# Sheet4.net
KiCad netlist of a schematic drawn in Altium Designer
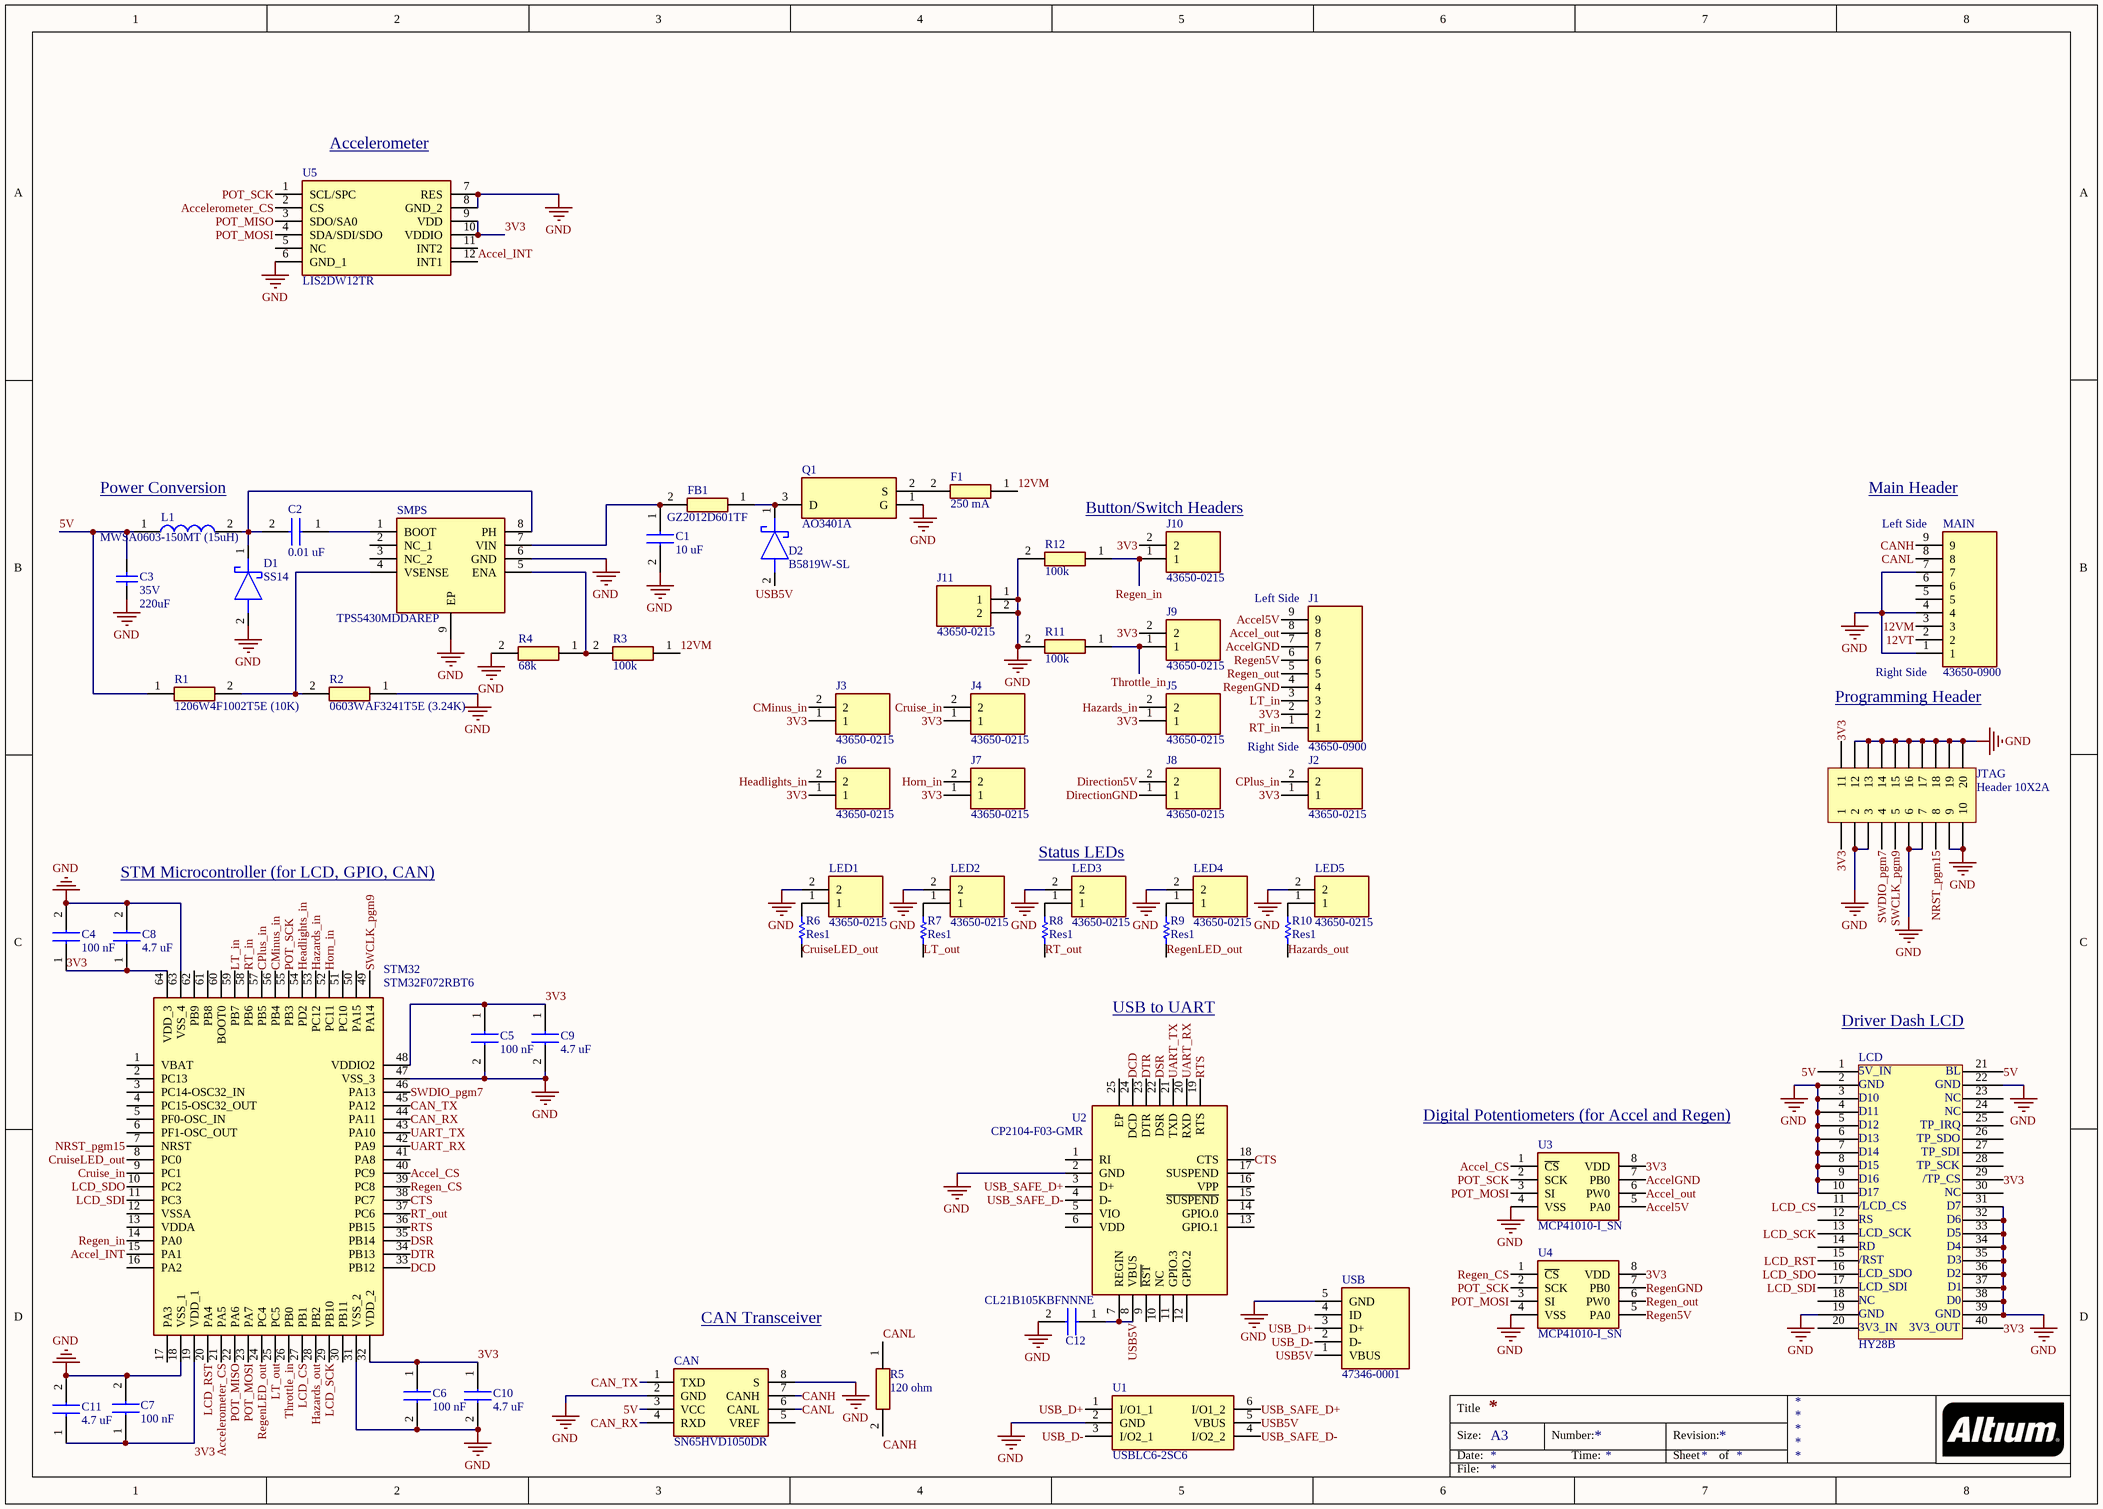
[diagram p0: Sheet4.SchDoc]

(export (version "E")
  (design (tool "Eeschema 10.0.6"))
  (components
    (comp (ref "C1")
      (value "10 uF")
      (footprint "SamacSys:CAPC2012X145N")
      (description "Capacitor")
      (fields (field (name "MANUFACTURER_PART_NUMBER") "CL21A106KAYNNNE"))
      (libsource (lib "*") (part "CL21A106KAYNNNE"))
    )
    (comp (ref "C2")
      (value "0.01 uF")
      (footprint "SamacSys:CAPC2012X65N")
      (description "Capacitor")
      (fields (field (name "MANUFACTURER_PART_NUMBER") "CL21B103KBANNNC"))
      (libsource (lib "*") (part "CL21B103KBANNNC"))
    )
    (comp (ref "C3")
      (value "35V")
      (footprint "RAD-0.3")
      (description "Capacitor")
      (fields (field (name "ALTIUM_VALUE") "220uF") (field (name "PUBLISHER") "Altium Limited"))
      (libsource (lib "Miscellaneous Devices") (part "Cap"))
    )
    (comp (ref "C4")
      (value "100 nF")
      (footprint "SamacSys:CAPC1005X55N")
      (description "Capacitor")
      (fields (field (name "MANUFACTURER_PART_NUMBER") "CL05B104KO5NNNC"))
      (libsource (lib "*") (part "CL05B104KO5NNNC"))
    )
    (comp (ref "C5")
      (value "100 nF")
      (footprint "SamacSys:CAPC1005X55N")
      (description "Capacitor")
      (fields (field (name "MANUFACTURER_PART_NUMBER") "CL05B104KO5NNNC"))
      (libsource (lib "*") (part "CL05B104KO5NNNC"))
    )
    (comp (ref "C6")
      (value "100 nF")
      (footprint "SamacSys:CAPC1005X55N")
      (description "Capacitor")
      (fields (field (name "MANUFACTURER_PART_NUMBER") "CL05B104KO5NNNC"))
      (libsource (lib "*") (part "CL05B104KO5NNNC"))
    )
    (comp (ref "C7")
      (value "100 nF")
      (footprint "SamacSys:CAPC1005X55N")
      (description "Capacitor")
      (fields (field (name "MANUFACTURER_PART_NUMBER") "CL05B104KO5NNNC"))
      (libsource (lib "*") (part "CL05B104KO5NNNC"))
    )
    (comp (ref "C8")
      (value "4.7 uF")
      (footprint "SamacSys:CAPC2012X140N")
      (description "Capacitor")
      (fields (field (name "MANUFACTURER_PART_NUMBER") "CL21A475KAQNNNE"))
      (libsource (lib "*") (part "CL21A475KAQNNNE"))
    )
    (comp (ref "C9")
      (value "4.7 uF")
      (footprint "SamacSys:CAPC2012X140N")
      (description "Capacitor")
      (fields (field (name "MANUFACTURER_PART_NUMBER") "CL21A475KAQNNNE"))
      (libsource (lib "*") (part "CL21A475KAQNNNE"))
    )
    (comp (ref "C10")
      (value "4.7 uF")
      (footprint "SamacSys:CAPC2012X140N")
      (description "Capacitor")
      (fields (field (name "MANUFACTURER_PART_NUMBER") "CL21A475KAQNNNE"))
      (libsource (lib "*") (part "CL21A475KAQNNNE"))
    )
    (comp (ref "C11")
      (value "4.7 uF")
      (footprint "SamacSys:CAPC2012X140N")
      (description "Capacitor")
      (fields (field (name "MANUFACTURER_PART_NUMBER") "CL21A475KAQNNNE"))
      (libsource (lib "*") (part "CL21A475KAQNNNE"))
    )
    (comp (ref "C12")
      (value "CL21B105KBFNNNE")
      (footprint "SamacSys:CAPC2012X135N")
      (description "Capacitor")
      (libsource (lib "*") (part "CL21B105KBFNNNE"))
    )
    (comp (ref "CAN")
      (value "SN65HVD1050DR")
      (footprint "SamacSys:SOIC127P600X175-8N")
      (description "Integrated Circuit")
      (libsource (lib "*") (part "SN65HVD1050DR"))
    )
    (comp (ref "D1")
      (value "SS14")
      (footprint "SamacSys:DIONM5327X242N")
      (description "Schottky Diode")
      (libsource (lib "*") (part "SS14"))
    )
    (comp (ref "D2")
      (value "B5819W-SL")
      (footprint "SamacSys:SOD3716X135N")
      (description "Schottky Diode")
      (fields (field (name "MANUFACTURER_PART_NUMBER") "B5819W-TP"))
      (libsource (lib "*") (part "B5819W-TP"))
    )
    (comp (ref "F1")
      (value "250 mA")
      (footprint "SamacSys:RESC3216X51N")
      (description "Resistor")
      (fields (field (name "MANUFACTURER_PART_NUMBER") "PHPA1206E2001BST1"))
      (libsource (lib "*") (part "PHPA1206E2001BST1"))
    )
    (comp (ref "FB1")
      (value "GZ2012D601TF")
      (footprint "SamacSys:RESC2012X55N")
      (description "Resistor")
      (fields (field (name "MANUFACTURER_PART_NUMBER") "TNPU080550K0AZEN00"))
      (libsource (lib "*") (part "TNPU080550K0AZEN00"))
    )
    (comp (ref "J1")
      (value "43650-0900")
      (footprint "SamacSys:436500900")
      (description "Connector")
      (libsource (lib "*") (part "43650-0900"))
    )
    (comp (ref "J2")
      (value "43650-0215")
      (footprint "SamacSys:43650-0217")
      (description "Connector")
      (fields (field (name "MOUSER2 PART NUMBER") "538-43650-0215"))
      (libsource (lib "*") (part "43650-0215"))
    )
    (comp (ref "J3")
      (value "43650-0215")
      (footprint "SamacSys:43650-0217")
      (description "Connector")
      (fields (field (name "MOUSER2 PART NUMBER") "538-43650-0215"))
      (libsource (lib "*") (part "43650-0215"))
    )
    (comp (ref "J4")
      (value "43650-0215")
      (footprint "SamacSys:43650-0217")
      (description "Connector")
      (fields (field (name "MOUSER2 PART NUMBER") "538-43650-0215"))
      (libsource (lib "*") (part "43650-0215"))
    )
    (comp (ref "J5")
      (value "43650-0215")
      (footprint "SamacSys:43650-0217")
      (description "Connector")
      (fields (field (name "MOUSER2 PART NUMBER") "538-43650-0215"))
      (libsource (lib "*") (part "43650-0215"))
    )
    (comp (ref "J6")
      (value "43650-0215")
      (footprint "SamacSys:43650-0217")
      (description "Connector")
      (fields (field (name "MOUSER2 PART NUMBER") "538-43650-0215"))
      (libsource (lib "*") (part "43650-0215"))
    )
    (comp (ref "J7")
      (value "43650-0215")
      (footprint "SamacSys:43650-0217")
      (description "Connector")
      (fields (field (name "MOUSER2 PART NUMBER") "538-43650-0215"))
      (libsource (lib "*") (part "43650-0215"))
    )
    (comp (ref "J8")
      (value "43650-0215")
      (footprint "SamacSys:43650-0217")
      (description "Connector")
      (fields (field (name "MOUSER2 PART NUMBER") "538-43650-0215"))
      (libsource (lib "*") (part "43650-0215"))
    )
    (comp (ref "J9")
      (value "43650-0215")
      (footprint "SamacSys:43650-0217")
      (description "Connector")
      (fields (field (name "MOUSER2 PART NUMBER") "538-43650-0215"))
      (libsource (lib "*") (part "43650-0215"))
    )
    (comp (ref "J10")
      (value "43650-0215")
      (footprint "SamacSys:43650-0217")
      (description "Connector")
      (fields (field (name "MOUSER2 PART NUMBER") "538-43650-0215"))
      (libsource (lib "*") (part "43650-0215"))
    )
    (comp (ref "J11")
      (value "43650-0215")
      (footprint "SamacSys:43650-0217")
      (description "Connector")
      (fields (field (name "MOUSER2 PART NUMBER") "538-43650-0215"))
      (libsource (lib "") (part "43650-0215_1"))
    )
    (comp (ref "JTAG")
      (value "Header 10X2A")
      (footprint "HDR2X10_CEN")
      (description "Header, 10-Pin, Dual row")
      (fields (field (name "PUBLISHER") "Altium Limited"))
      (libsource (lib "Miscellaneous Connectors") (part "Header 10X2A"))
    )
    (comp (ref "L1")
      (value "MWSA0603-150MT (15uH)")
      (footprint "SamacSys:INDPM7166X300N")
      (description "Inductor")
      (fields (field (name "MANUFACTURER_PART_NUMBER") "SRP7028AA-220M"))
      (libsource (lib "*") (part "SRP7028AA-220M"))
    )
    (comp (ref "LCD")
      (value "HY28B")
      (footprint "HY28B")
      (description "2.8\" LCD")
      (libsource (lib "SteeringWheelParts") (part "HY28B"))
    )
    (comp (ref "LED1")
      (value "43650-0215")
      (footprint "SamacSys:43650-0217")
      (description "Connector")
      (fields (field (name "MOUSER2 PART NUMBER") "538-43650-0215"))
      (libsource (lib "*") (part "43650-0215"))
    )
    (comp (ref "LED2")
      (value "43650-0215")
      (footprint "SamacSys:43650-0217")
      (description "Connector")
      (fields (field (name "MOUSER2 PART NUMBER") "538-43650-0215"))
      (libsource (lib "*") (part "43650-0215"))
    )
    (comp (ref "LED3")
      (value "43650-0215")
      (footprint "SamacSys:43650-0217")
      (description "Connector")
      (fields (field (name "MOUSER2 PART NUMBER") "538-43650-0215"))
      (libsource (lib "*") (part "43650-0215"))
    )
    (comp (ref "LED4")
      (value "43650-0215")
      (footprint "SamacSys:43650-0217")
      (description "Connector")
      (fields (field (name "MOUSER2 PART NUMBER") "538-43650-0215"))
      (libsource (lib "*") (part "43650-0215"))
    )
    (comp (ref "LED5")
      (value "43650-0215")
      (footprint "SamacSys:43650-0217")
      (description "Connector")
      (fields (field (name "MOUSER2 PART NUMBER") "538-43650-0215"))
      (libsource (lib "*") (part "43650-0215"))
    )
    (comp (ref "MAIN")
      (value "43650-0900")
      (footprint "SamacSys:436500900")
      (description "Connector")
      (libsource (lib "*") (part "43650-0900"))
    )
    (comp (ref "Q1")
      (value "AO3401A")
      (footprint "SamacSys:SOT95P237X115-3N")
      (description "Diode ESD (Bi-directional)")
      (fields (field (name "MANUFACTURER_PART_NUMBER") "AQ3102-02HTG"))
      (libsource (lib "*") (part "AQ3102-02HTG"))
    )
    (comp (ref "R1")
      (value "1206W4F1002T5E (10K)")
      (footprint "SamacSys:RESC3216X75N")
      (description "Resistor")
      (fields (field (name "MANUFACTURER_PART_NUMBER") "CR1206-FW-2214ELF"))
      (libsource (lib "*") (part "CR1206-FW-2214ELF"))
    )
    (comp (ref "R2")
      (value "0603WAF3241T5E (3.24K)")
      (footprint "SamacSys:RESC1608X55N")
      (description "Resistor")
      (fields (field (name "MANUFACTURER_PART_NUMBER") "MCT0603MZ0000ZP500"))
      (libsource (lib "") (part "MCT0603MZ0000ZP500_1"))
    )
    (comp (ref "R3")
      (value "100k")
      (footprint "SamacSys:RESC3216X51N")
      (description "Resistor")
      (fields (field (name "MANUFACTURER_PART_NUMBER") "PHPA1206E2001BST1"))
      (libsource (lib "*") (part "PHPA1206E2001BST1"))
    )
    (comp (ref "R4")
      (value "68k")
      (footprint "SamacSys:RESC1608X55N")
      (description "Resistor")
      (fields (field (name "MANUFACTURER_PART_NUMBER") "MCT0603MZ0000ZP500"))
      (libsource (lib "") (part "MCT0603MZ0000ZP500_1"))
    )
    (comp (ref "R5")
      (value "120 ohm")
      (footprint "SamacSys:RESC1608X55N")
      (description "Resistor")
      (fields (field (name "MANUFACTURER_PART_NUMBER") "MCT0603MZ0000ZP500"))
      (libsource (lib "*") (part "MCT0603MZ0000ZP500"))
    )
    (comp (ref "R6")
      (value "Res1")
      (footprint "AXIAL-0.3")
      (description "Resistor")
      (fields (field (name "PUBLISHER") "Altium Limited"))
      (libsource (lib "Miscellaneous Devices") (part "Res1"))
    )
    (comp (ref "R7")
      (value "Res1")
      (footprint "AXIAL-0.3")
      (description "Resistor")
      (fields (field (name "PUBLISHER") "Altium Limited"))
      (libsource (lib "Miscellaneous Devices") (part "Res1"))
    )
    (comp (ref "R8")
      (value "Res1")
      (footprint "AXIAL-0.3")
      (description "Resistor")
      (fields (field (name "PUBLISHER") "Altium Limited"))
      (libsource (lib "Miscellaneous Devices") (part "Res1"))
    )
    (comp (ref "R9")
      (value "Res1")
      (footprint "AXIAL-0.3")
      (description "Resistor")
      (fields (field (name "PUBLISHER") "Altium Limited"))
      (libsource (lib "Miscellaneous Devices") (part "Res1"))
    )
    (comp (ref "R10")
      (value "Res1")
      (footprint "AXIAL-0.3")
      (description "Resistor")
      (fields (field (name "PUBLISHER") "Altium Limited"))
      (libsource (lib "Miscellaneous Devices") (part "Res1"))
    )
    (comp (ref "R11")
      (value "100k")
      (footprint "SamacSys:RESC3216X51N")
      (description "Resistor")
      (fields (field (name "MANUFACTURER_PART_NUMBER") "PHPA1206E2001BST1"))
      (libsource (lib "*") (part "PHPA1206E2001BST1"))
    )
    (comp (ref "R12")
      (value "100k")
      (footprint "SamacSys:RESC3216X51N")
      (description "Resistor")
      (fields (field (name "MANUFACTURER_PART_NUMBER") "PHPA1206E2001BST1"))
      (libsource (lib "*") (part "PHPA1206E2001BST1"))
    )
    (comp (ref "SMPS")
      (value "TPS5430MDDAREP")
      (footprint "SamacSys:SOIC127P600X170-9N")
      (description "Integrated Circuit")
      (fields (field (name "MOUSER2 PART NUMBER") "595-TPS5430MDDAREP"))
      (libsource (lib "*") (part "TPS5430MDDAREP"))
    )
    (comp (ref "STM32")
      (value "STM32F072RBT6")
      (footprint "SamacSys:QFP50P1200X1200X160-64N")
      (description "Integrated Circuit")
      (fields (field (name "MOUSER2 PART NUMBER") "511-STM32F072RBT6"))
      (libsource (lib "*") (part "STM32F072RBT6"))
    )
    (comp (ref "U1")
      (value "USBLC6-2SC6")
      (footprint "SamacSys:SOT95P280X145-6N")
      (description "Integrated Circuit")
      (fields (field (name "MOUSER2 PART NUMBER") "511-USBLC6-2SC6"))
      (libsource (lib "*") (part "USBLC6-2SC6"))
    )
    (comp (ref "U2")
      (value "CP2104-F03-GMR")
      (footprint "SamacSys:QFN50P400X400X80-25N-D")
      (description "Integrated Circuit")
      (fields (field (name "MOUSER2 PART NUMBER") "634-CP2104-F03-GMR"))
      (libsource (lib "*") (part "CP2104-F03-GMR"))
    )
    (comp (ref "U3")
      (value "MCP41010-I_SN")
      (footprint "SamacSys:SOIC127P600X175-8N")
      (description "Integrated Circuit")
      (fields
        (field (name "MOUSER2 PART NUMBER") "579-MCP41010-I/SN")
        (field (name "MANUFACTURER_PART_NUMBER") "MCP41010-I/SN")
      )
      (libsource (lib "*") (part "MCP41010-I_SN"))
    )
    (comp (ref "U4")
      (value "MCP41010-I_SN")
      (footprint "SamacSys:SOIC127P600X175-8N")
      (description "Integrated Circuit")
      (fields
        (field (name "MOUSER2 PART NUMBER") "579-MCP41010-I/SN")
        (field (name "MANUFACTURER_PART_NUMBER") "MCP41010-I/SN")
      )
      (libsource (lib "*") (part "MCP41010-I_SN"))
    )
    (comp (ref "U5")
      (value "LIS2DW12TR")
      (footprint "SamacSys:LGA-12")
      (description "Integrated Circuit")
      (fields (field (name "MOUSER2 PART NUMBER") "511-LIS2DW12TR"))
      (libsource (lib "*") (part "LIS2DW12TR"))
    )
    (comp (ref "USB")
      (value "47346-0001")
      (footprint "SamacSys:47346-0001")
      (description "Connector")
      (libsource (lib "*") (part "47346-0001"))
    )
  )
  (nets
    (net (code "1") (name "/3V3") (class "Default")
      (node (ref "C10") (pin "1") (pinfunction "1_1") (pintype "passive"))
      (node (ref "C11") (pin "1") (pinfunction "1_1") (pintype "passive"))
      (node (ref "C4") (pin "1") (pinfunction "1_1") (pintype "passive"))
      (node (ref "C5") (pin "1") (pinfunction "1_1") (pintype "passive"))
      (node (ref "C6") (pin "1") (pinfunction "1_1") (pintype "passive"))
      (node (ref "C7") (pin "1") (pinfunction "1_1") (pintype "passive"))
      (node (ref "C8") (pin "1") (pinfunction "1_1") (pintype "passive"))
      (node (ref "C9") (pin "1") (pinfunction "1_1") (pintype "passive"))
      (node (ref "J1") (pin "2") (pinfunction "2_2") (pintype "passive"))
      (node (ref "J10") (pin "2") (pinfunction "2_2") (pintype "passive"))
      (node (ref "J2") (pin "1") (pinfunction "1_1") (pintype "passive"))
      (node (ref "J3") (pin "1") (pinfunction "1_1") (pintype "passive"))
      (node (ref "J4") (pin "1") (pinfunction "1_1") (pintype "passive"))
      (node (ref "J5") (pin "1") (pinfunction "1_1") (pintype "passive"))
      (node (ref "J6") (pin "1") (pinfunction "1_1") (pintype "passive"))
      (node (ref "J7") (pin "1") (pinfunction "1_1") (pintype "passive"))
      (node (ref "J9") (pin "2") (pinfunction "2_2") (pintype "passive"))
      (node (ref "JTAG") (pin "1") (pinfunction "1_1") (pintype "passive"))
      (node (ref "JTAG") (pin "11") (pinfunction "11_11") (pintype "passive"))
      (node (ref "LCD") (pin "29") (pinfunction "29_29") (pintype "passive"))
      (node (ref "LCD") (pin "40") (pinfunction "40_40") (pintype "passive"))
      (node (ref "STM32") (pin "19") (pinfunction "VDD_1_19") (pintype "passive"))
      (node (ref "STM32") (pin "32") (pinfunction "VDD_2_32") (pintype "passive"))
      (node (ref "STM32") (pin "48") (pinfunction "VDDIO2_48") (pintype "passive"))
      (node (ref "STM32") (pin "64") (pinfunction "VDD_3_64") (pintype "passive"))
      (node (ref "U3") (pin "8") (pinfunction "VDD_8") (pintype "passive"))
      (node (ref "U4") (pin "8") (pinfunction "VDD_8") (pintype "passive"))
      (node (ref "U5") (pin "10") (pinfunction "VDDIO_10") (pintype "passive"))
      (node (ref "U5") (pin "9") (pinfunction "VDD_9") (pintype "passive"))
    )
    (net (code "2") (name "/5V") (class "Default")
      (node (ref "C3") (pin "2") (pinfunction "2_2") (pintype "passive"))
      (node (ref "CAN") (pin "3") (pinfunction "VCC_3") (pintype "passive"))
      (node (ref "L1") (pin "1") (pinfunction "1_1") (pintype "passive"))
      (node (ref "LCD") (pin "1") (pinfunction "1_1") (pintype "passive"))
      (node (ref "LCD") (pin "21") (pinfunction "21_21") (pintype "passive"))
      (node (ref "R1") (pin "1") (pinfunction "1_1") (pintype "passive"))
    )
    (net (code "3") (name "/12VM") (class "Default")
      (node (ref "F1") (pin "1") (pinfunction "1_1") (pintype "passive"))
      (node (ref "MAIN") (pin "3") (pinfunction "3_3") (pintype "passive"))
      (node (ref "R3") (pin "1") (pinfunction "1_1") (pintype "passive"))
    )
    (net (code "4") (name "/12VT") (class "Default")
      (node (ref "MAIN") (pin "2") (pinfunction "2_2") (pintype "passive"))
    )
    (net (code "5") (name "/Accel5V") (class "Default")
      (node (ref "J1") (pin "9") (pinfunction "9_9") (pintype "passive"))
      (node (ref "U3") (pin "5") (pinfunction "PA0_5") (pintype "passive"))
    )
    (net (code "6") (name "/AccelGND") (class "Default")
      (node (ref "J1") (pin "7") (pinfunction "7_7") (pintype "passive"))
      (node (ref "U3") (pin "7") (pinfunction "PB0_7") (pintype "passive"))
    )
    (net (code "7") (name "/Accel_CS") (class "Default")
      (node (ref "STM32") (pin "40") (pinfunction "PC9_40") (pintype "passive"))
      (node (ref "U3") (pin "1") (pinfunction "~{CS}_1") (pintype "passive"))
    )
    (net (code "8") (name "/Accel_INT") (class "Default")
      (node (ref "STM32") (pin "15") (pinfunction "PA1_15") (pintype "passive"))
      (node (ref "U5") (pin "12") (pinfunction "INT1_12") (pintype "passive"))
    )
    (net (code "9") (name "/Accel_out") (class "Default")
      (node (ref "J1") (pin "8") (pinfunction "8_8") (pintype "passive"))
      (node (ref "U3") (pin "6") (pinfunction "PW0_6") (pintype "passive"))
    )
    (net (code "10") (name "/Accelerometer_CS") (class "Default")
      (node (ref "STM32") (pin "21") (pinfunction "PA5_21") (pintype "passive"))
      (node (ref "U5") (pin "2") (pinfunction "CS_2") (pintype "passive"))
    )
    (net (code "11") (name "/CANH") (class "Default")
      (node (ref "CAN") (pin "7") (pinfunction "CANH_7") (pintype "passive"))
      (node (ref "MAIN") (pin "9") (pinfunction "9_9") (pintype "passive"))
      (node (ref "R5") (pin "2") (pinfunction "2_2") (pintype "passive"))
    )
    (net (code "12") (name "/CANL") (class "Default")
      (node (ref "CAN") (pin "6") (pinfunction "CANL_6") (pintype "passive"))
      (node (ref "MAIN") (pin "8") (pinfunction "8_8") (pintype "passive"))
      (node (ref "R5") (pin "1") (pinfunction "1_1") (pintype "passive"))
    )
    (net (code "13") (name "/CAN_RX") (class "Default")
      (node (ref "CAN") (pin "4") (pinfunction "RXD_4") (pintype "passive"))
      (node (ref "STM32") (pin "44") (pinfunction "PA11_44") (pintype "passive"))
    )
    (net (code "14") (name "/CAN_TX") (class "Default")
      (node (ref "CAN") (pin "1") (pinfunction "TXD_1") (pintype "passive"))
      (node (ref "STM32") (pin "45") (pinfunction "PA12_45") (pintype "passive"))
    )
    (net (code "15") (name "/CMinus_in") (class "Default")
      (node (ref "J3") (pin "2") (pinfunction "2_2") (pintype "passive"))
      (node (ref "STM32") (pin "56") (pinfunction "PB4_56") (pintype "passive"))
    )
    (net (code "16") (name "/CPlus_in") (class "Default")
      (node (ref "J2") (pin "2") (pinfunction "2_2") (pintype "passive"))
      (node (ref "STM32") (pin "57") (pinfunction "PB5_57") (pintype "passive"))
    )
    (net (code "17") (name "/CTS") (class "Default")
      (node (ref "STM32") (pin "38") (pinfunction "PC7_38") (pintype "passive"))
      (node (ref "U2") (pin "18") (pinfunction "CTS_18") (pintype "passive"))
    )
    (net (code "18") (name "/CruiseLED_out") (class "Default")
      (node (ref "R6") (pin "1") (pinfunction "1_1") (pintype "passive"))
      (node (ref "STM32") (pin "8") (pinfunction "PC0_8") (pintype "passive"))
    )
    (net (code "19") (name "/Cruise_in") (class "Default")
      (node (ref "J4") (pin "2") (pinfunction "2_2") (pintype "passive"))
      (node (ref "STM32") (pin "9") (pinfunction "PC1_9") (pintype "passive"))
    )
    (net (code "20") (name "/DCD") (class "Default")
      (node (ref "STM32") (pin "33") (pinfunction "PB12_33") (pintype "passive"))
      (node (ref "U2") (pin "24") (pinfunction "DCD_24") (pintype "passive"))
    )
    (net (code "21") (name "/DSR") (class "Default")
      (node (ref "STM32") (pin "35") (pinfunction "PB14_35") (pintype "passive"))
      (node (ref "U2") (pin "22") (pinfunction "DSR_22") (pintype "passive"))
    )
    (net (code "22") (name "/DTR") (class "Default")
      (node (ref "STM32") (pin "34") (pinfunction "PB13_34") (pintype "passive"))
      (node (ref "U2") (pin "23") (pinfunction "DTR_23") (pintype "passive"))
    )
    (net (code "23") (name "/Direction5V") (class "Default")
      (node (ref "J8") (pin "2") (pinfunction "2_2") (pintype "passive"))
    )
    (net (code "24") (name "/DirectionGND") (class "Default")
      (node (ref "J8") (pin "1") (pinfunction "1_1") (pintype "passive"))
    )
    (net (code "25") (name "/Hazards_in") (class "Default")
      (node (ref "J5") (pin "2") (pinfunction "2_2") (pintype "passive"))
      (node (ref "STM32") (pin "53") (pinfunction "PC12_53") (pintype "passive"))
    )
    (net (code "26") (name "/Hazards_out") (class "Default")
      (node (ref "R10") (pin "1") (pinfunction "1_1") (pintype "passive"))
      (node (ref "STM32") (pin "28") (pinfunction "PB2_28") (pintype "passive"))
    )
    (net (code "27") (name "/Headlights_in") (class "Default")
      (node (ref "J6") (pin "2") (pinfunction "2_2") (pintype "passive"))
      (node (ref "STM32") (pin "54") (pinfunction "PD2_54") (pintype "passive"))
    )
    (net (code "28") (name "/Horn_in") (class "Default")
      (node (ref "J7") (pin "2") (pinfunction "2_2") (pintype "passive"))
      (node (ref "STM32") (pin "52") (pinfunction "PC11_52") (pintype "passive"))
    )
    (net (code "29") (name "/LCD_CS") (class "Default")
      (node (ref "LCD") (pin "11") (pinfunction "11_11") (pintype "passive"))
      (node (ref "STM32") (pin "27") (pinfunction "PB1_27") (pintype "passive"))
    )
    (net (code "30") (name "/LCD_RST") (class "Default")
      (node (ref "LCD") (pin "15") (pinfunction "15_15") (pintype "passive"))
      (node (ref "STM32") (pin "20") (pinfunction "PA4_20") (pintype "passive"))
    )
    (net (code "31") (name "/LCD_SCK") (class "Default")
      (node (ref "LCD") (pin "13") (pinfunction "13_13") (pintype "passive"))
      (node (ref "STM32") (pin "29") (pinfunction "PB10_29") (pintype "passive"))
    )
    (net (code "32") (name "/LCD_SDI") (class "Default")
      (node (ref "LCD") (pin "17") (pinfunction "17_17") (pintype "passive"))
      (node (ref "STM32") (pin "11") (pinfunction "PC3_11") (pintype "passive"))
    )
    (net (code "33") (name "/LCD_SDO") (class "Default")
      (node (ref "LCD") (pin "16") (pinfunction "16_16") (pintype "passive"))
      (node (ref "STM32") (pin "10") (pinfunction "PC2_10") (pintype "passive"))
    )
    (net (code "34") (name "/LT_in") (class "Default")
      (node (ref "J1") (pin "3") (pinfunction "3_3") (pintype "passive"))
      (node (ref "STM32") (pin "59") (pinfunction "PB7_59") (pintype "passive"))
    )
    (net (code "35") (name "/LT_out") (class "Default")
      (node (ref "R7") (pin "1") (pinfunction "1_1") (pintype "passive"))
      (node (ref "STM32") (pin "25") (pinfunction "PC5_25") (pintype "passive"))
    )
    (net (code "36") (name "/NRST_pgm15") (class "Default")
      (node (ref "JTAG") (pin "8") (pinfunction "8_8") (pintype "passive"))
      (node (ref "STM32") (pin "7") (pinfunction "NRST_7") (pintype "passive"))
    )
    (net (code "37") (name "/POT_MISO") (class "Default")
      (node (ref "STM32") (pin "22") (pinfunction "PA6_22") (pintype "passive"))
      (node (ref "U5") (pin "3") (pinfunction "SDO/SA0_3") (pintype "passive"))
    )
    (net (code "38") (name "/POT_MOSI") (class "Default")
      (node (ref "STM32") (pin "23") (pinfunction "PA7_23") (pintype "passive"))
      (node (ref "U3") (pin "3") (pinfunction "SI_3") (pintype "passive"))
      (node (ref "U4") (pin "3") (pinfunction "SI_3") (pintype "passive"))
      (node (ref "U5") (pin "4") (pinfunction "SDA/SDI/SDO_4") (pintype "passive"))
    )
    (net (code "39") (name "/POT_SCK") (class "Default")
      (node (ref "STM32") (pin "55") (pinfunction "PB3_55") (pintype "passive"))
      (node (ref "U3") (pin "2") (pinfunction "SCK_2") (pintype "passive"))
      (node (ref "U4") (pin "2") (pinfunction "SCK_2") (pintype "passive"))
      (node (ref "U5") (pin "1") (pinfunction "SCL/SPC_1") (pintype "passive"))
    )
    (net (code "40") (name "/RTS") (class "Default")
      (node (ref "STM32") (pin "36") (pinfunction "PB15_36") (pintype "passive"))
      (node (ref "U2") (pin "19") (pinfunction "RTS_19") (pintype "passive"))
    )
    (net (code "41") (name "/RT_in") (class "Default")
      (node (ref "J1") (pin "1") (pinfunction "1_1") (pintype "passive"))
      (node (ref "STM32") (pin "58") (pinfunction "PB6_58") (pintype "passive"))
    )
    (net (code "42") (name "/RT_out") (class "Default")
      (node (ref "R8") (pin "1") (pinfunction "1_1") (pintype "passive"))
      (node (ref "STM32") (pin "37") (pinfunction "PC6_37") (pintype "passive"))
    )
    (net (code "43") (name "/Regen5V") (class "Default")
      (node (ref "J1") (pin "6") (pinfunction "6_6") (pintype "passive"))
      (node (ref "U4") (pin "5") (pinfunction "PA0_5") (pintype "passive"))
    )
    (net (code "44") (name "/RegenGND") (class "Default")
      (node (ref "J1") (pin "4") (pinfunction "4_4") (pintype "passive"))
      (node (ref "U4") (pin "7") (pinfunction "PB0_7") (pintype "passive"))
    )
    (net (code "45") (name "/RegenLED_out") (class "Default")
      (node (ref "R9") (pin "1") (pinfunction "1_1") (pintype "passive"))
      (node (ref "STM32") (pin "24") (pinfunction "PC4_24") (pintype "passive"))
    )
    (net (code "46") (name "/Regen_CS") (class "Default")
      (node (ref "STM32") (pin "39") (pinfunction "PC8_39") (pintype "passive"))
      (node (ref "U4") (pin "1") (pinfunction "~{CS}_1") (pintype "passive"))
    )
    (net (code "47") (name "/Regen_in") (class "Default")
      (node (ref "J10") (pin "1") (pinfunction "1_1") (pintype "passive"))
      (node (ref "R12") (pin "1") (pinfunction "1_1") (pintype "passive"))
      (node (ref "STM32") (pin "14") (pinfunction "PA0_14") (pintype "passive"))
    )
    (net (code "48") (name "/Regen_out") (class "Default")
      (node (ref "J1") (pin "5") (pinfunction "5_5") (pintype "passive"))
      (node (ref "U4") (pin "6") (pinfunction "PW0_6") (pintype "passive"))
    )
    (net (code "49") (name "/SWCLK_pgm9") (class "Default")
      (node (ref "JTAG") (pin "5") (pinfunction "5_5") (pintype "passive"))
      (node (ref "STM32") (pin "49") (pinfunction "PA14_49") (pintype "passive"))
    )
    (net (code "50") (name "/SWDIO_pgm7") (class "Default")
      (node (ref "JTAG") (pin "4") (pinfunction "4_4") (pintype "passive"))
      (node (ref "STM32") (pin "46") (pinfunction "PA13_46") (pintype "passive"))
    )
    (net (code "51") (name "/Throttle_in") (class "Default")
      (node (ref "J9") (pin "1") (pinfunction "1_1") (pintype "passive"))
      (node (ref "R11") (pin "1") (pinfunction "1_1") (pintype "passive"))
      (node (ref "STM32") (pin "26") (pinfunction "PB0_26") (pintype "passive"))
    )
    (net (code "52") (name "/UART_RX") (class "Default")
      (node (ref "STM32") (pin "42") (pinfunction "PA9_42") (pintype "passive"))
      (node (ref "U2") (pin "20") (pinfunction "RXD_20") (pintype "passive"))
    )
    (net (code "53") (name "/UART_TX") (class "Default")
      (node (ref "STM32") (pin "43") (pinfunction "PA10_43") (pintype "passive"))
      (node (ref "U2") (pin "21") (pinfunction "TXD_21") (pintype "passive"))
    )
    (net (code "54") (name "/USB5V") (class "Default")
      (node (ref "C12") (pin "1") (pinfunction "1_1") (pintype "passive"))
      (node (ref "D2") (pin "2") (pinfunction "A_2") (pintype "passive"))
      (node (ref "U1") (pin "5") (pinfunction "VBUS_5") (pintype "passive"))
      (node (ref "U2") (pin "7") (pinfunction "REGIN_7") (pintype "passive"))
      (node (ref "U2") (pin "8") (pinfunction "VBUS_8") (pintype "passive"))
      (node (ref "USB") (pin "1") (pinfunction "VBUS_1") (pintype "passive"))
    )
    (net (code "55") (name "/USB_D+") (class "Default")
      (node (ref "U1") (pin "1") (pinfunction "I/O1_1_1") (pintype "passive"))
      (node (ref "USB") (pin "3") (pinfunction "D+_3") (pintype "passive"))
    )
    (net (code "56") (name "/USB_D-") (class "Default")
      (node (ref "U1") (pin "3") (pinfunction "I/O2_1_3") (pintype "passive"))
      (node (ref "USB") (pin "2") (pinfunction "D-_2") (pintype "passive"))
    )
    (net (code "57") (name "/USB_SAFE_D+") (class "Default")
      (node (ref "U1") (pin "6") (pinfunction "I/O1_2_6") (pintype "passive"))
      (node (ref "U2") (pin "3") (pinfunction "D+_3") (pintype "passive"))
    )
    (net (code "58") (name "/USB_SAFE_D-") (class "Default")
      (node (ref "U1") (pin "4") (pinfunction "I/O2_2_4") (pintype "passive"))
      (node (ref "U2") (pin "4") (pinfunction "D-_4") (pintype "passive"))
    )
    (net (code "59") (name "GND") (class "Default")
      (node (ref "C1") (pin "2") (pinfunction "2_2") (pintype "passive"))
      (node (ref "C10") (pin "2") (pinfunction "2_2") (pintype "passive"))
      (node (ref "C11") (pin "2") (pinfunction "2_2") (pintype "passive"))
      (node (ref "C12") (pin "2") (pinfunction "2_2") (pintype "passive"))
      (node (ref "C3") (pin "1") (pinfunction "1_1") (pintype "passive"))
      (node (ref "C4") (pin "2") (pinfunction "2_2") (pintype "passive"))
      (node (ref "C5") (pin "2") (pinfunction "2_2") (pintype "passive"))
      (node (ref "C6") (pin "2") (pinfunction "2_2") (pintype "passive"))
      (node (ref "C7") (pin "2") (pinfunction "2_2") (pintype "passive"))
      (node (ref "C8") (pin "2") (pinfunction "2_2") (pintype "passive"))
      (node (ref "C9") (pin "2") (pinfunction "2_2") (pintype "passive"))
      (node (ref "CAN") (pin "2") (pinfunction "GND_2") (pintype "passive"))
      (node (ref "CAN") (pin "8") (pinfunction "S_8") (pintype "passive"))
      (node (ref "D1") (pin "2") (pinfunction "A_2") (pintype "passive"))
      (node (ref "J11") (pin "1") (pinfunction "1_1") (pintype "passive"))
      (node (ref "J11") (pin "2") (pinfunction "2_2") (pintype "passive"))
      (node (ref "JTAG") (pin "10") (pinfunction "10_10") (pintype "passive"))
      (node (ref "JTAG") (pin "12") (pinfunction "12_12") (pintype "passive"))
      (node (ref "JTAG") (pin "13") (pinfunction "13_13") (pintype "passive"))
      (node (ref "JTAG") (pin "14") (pinfunction "14_14") (pintype "passive"))
      (node (ref "JTAG") (pin "15") (pinfunction "15_15") (pintype "passive"))
      (node (ref "JTAG") (pin "16") (pinfunction "16_16") (pintype "passive"))
      (node (ref "JTAG") (pin "17") (pinfunction "17_17") (pintype "passive"))
      (node (ref "JTAG") (pin "18") (pinfunction "18_18") (pintype "passive"))
      (node (ref "JTAG") (pin "19") (pinfunction "19_19") (pintype "passive"))
      (node (ref "JTAG") (pin "2") (pinfunction "2_2") (pintype "passive"))
      (node (ref "JTAG") (pin "20") (pinfunction "20_20") (pintype "passive"))
      (node (ref "JTAG") (pin "3") (pinfunction "3_3") (pintype "passive"))
      (node (ref "JTAG") (pin "6") (pinfunction "6_6") (pintype "passive"))
      (node (ref "JTAG") (pin "7") (pinfunction "7_7") (pintype "passive"))
      (node (ref "JTAG") (pin "9") (pinfunction "9_9") (pintype "passive"))
      (node (ref "LCD") (pin "10") (pinfunction "10_10") (pintype "passive"))
      (node (ref "LCD") (pin "19") (pinfunction "19_19") (pintype "passive"))
      (node (ref "LCD") (pin "2") (pinfunction "2_2") (pintype "passive"))
      (node (ref "LCD") (pin "22") (pinfunction "22_22") (pintype "passive"))
      (node (ref "LCD") (pin "3") (pinfunction "3_3") (pintype "passive"))
      (node (ref "LCD") (pin "31") (pinfunction "31_31") (pintype "passive"))
      (node (ref "LCD") (pin "32") (pinfunction "32_32") (pintype "passive"))
      (node (ref "LCD") (pin "33") (pinfunction "33_33") (pintype "passive"))
      (node (ref "LCD") (pin "34") (pinfunction "34_34") (pintype "passive"))
      (node (ref "LCD") (pin "35") (pinfunction "35_35") (pintype "passive"))
      (node (ref "LCD") (pin "36") (pinfunction "36_36") (pintype "passive"))
      (node (ref "LCD") (pin "37") (pinfunction "37_37") (pintype "passive"))
      (node (ref "LCD") (pin "38") (pinfunction "38_38") (pintype "passive"))
      (node (ref "LCD") (pin "39") (pinfunction "39_39") (pintype "passive"))
      (node (ref "LCD") (pin "4") (pinfunction "4_4") (pintype "passive"))
      (node (ref "LCD") (pin "5") (pinfunction "5_5") (pintype "passive"))
      (node (ref "LCD") (pin "6") (pinfunction "6_6") (pintype "passive"))
      (node (ref "LCD") (pin "7") (pinfunction "7_7") (pintype "passive"))
      (node (ref "LCD") (pin "8") (pinfunction "8_8") (pintype "passive"))
      (node (ref "LCD") (pin "9") (pinfunction "9_9") (pintype "passive"))
      (node (ref "LED1") (pin "2") (pinfunction "2_2") (pintype "passive"))
      (node (ref "LED2") (pin "2") (pinfunction "2_2") (pintype "passive"))
      (node (ref "LED3") (pin "2") (pinfunction "2_2") (pintype "passive"))
      (node (ref "LED4") (pin "2") (pinfunction "2_2") (pintype "passive"))
      (node (ref "LED5") (pin "2") (pinfunction "2_2") (pintype "passive"))
      (node (ref "MAIN") (pin "1") (pinfunction "1_1") (pintype "passive"))
      (node (ref "MAIN") (pin "4") (pinfunction "4_4") (pintype "passive"))
      (node (ref "MAIN") (pin "7") (pinfunction "7_7") (pintype "passive"))
      (node (ref "Q1") (pin "1") (pinfunction "G_1") (pintype "passive"))
      (node (ref "R11") (pin "2") (pinfunction "2_2") (pintype "passive"))
      (node (ref "R12") (pin "2") (pinfunction "2_2") (pintype "passive"))
      (node (ref "R2") (pin "1") (pinfunction "1_1") (pintype "passive"))
      (node (ref "R4") (pin "2") (pinfunction "2_2") (pintype "passive"))
      (node (ref "SMPS") (pin "6") (pinfunction "GND_6") (pintype "passive"))
      (node (ref "SMPS") (pin "9") (pinfunction "EP_9") (pintype "passive"))
      (node (ref "STM32") (pin "18") (pinfunction "VSS_1_18") (pintype "passive"))
      (node (ref "STM32") (pin "31") (pinfunction "VSS_2_31") (pintype "passive"))
      (node (ref "STM32") (pin "47") (pinfunction "VSS_3_47") (pintype "passive"))
      (node (ref "STM32") (pin "63") (pinfunction "VSS_4_63") (pintype "passive"))
      (node (ref "U1") (pin "2") (pinfunction "GND_2") (pintype "passive"))
      (node (ref "U2") (pin "2") (pinfunction "GND_2") (pintype "passive"))
      (node (ref "U3") (pin "4") (pinfunction "VSS_4") (pintype "passive"))
      (node (ref "U4") (pin "4") (pinfunction "VSS_4") (pintype "passive"))
      (node (ref "U5") (pin "6") (pinfunction "GND_1_6") (pintype "passive"))
      (node (ref "U5") (pin "7") (pinfunction "RES_7") (pintype "passive"))
      (node (ref "U5") (pin "8") (pinfunction "GND_2_8") (pintype "passive"))
      (node (ref "USB") (pin "5") (pinfunction "GND_5") (pintype "passive"))
    )
    (net (code "60") (name "Net-(D1-K)") (class "Default")
      (node (ref "C2") (pin "2") (pinfunction "2_2") (pintype "passive"))
      (node (ref "D1") (pin "1") (pinfunction "K_1") (pintype "passive"))
      (node (ref "L1") (pin "2") (pinfunction "2_2") (pintype "passive"))
      (node (ref "SMPS") (pin "8") (pinfunction "PH_8") (pintype "passive"))
    )
    (net (code "61") (name "Net-(D2-K)") (class "Default")
      (node (ref "D2") (pin "1") (pinfunction "K_1") (pintype "passive"))
      (node (ref "FB1") (pin "1") (pinfunction "1_1") (pintype "passive"))
      (node (ref "Q1") (pin "3") (pinfunction "D_3") (pintype "passive"))
    )
    (net (code "62") (name "Net-(LED1-Pad1)") (class "Default")
      (node (ref "LED1") (pin "1") (pinfunction "1_1") (pintype "passive"))
      (node (ref "R6") (pin "2") (pinfunction "2_2") (pintype "passive"))
    )
    (net (code "63") (name "Net-(LED2-Pad1)") (class "Default")
      (node (ref "LED2") (pin "1") (pinfunction "1_1") (pintype "passive"))
      (node (ref "R7") (pin "2") (pinfunction "2_2") (pintype "passive"))
    )
    (net (code "64") (name "Net-(LED3-Pad1)") (class "Default")
      (node (ref "LED3") (pin "1") (pinfunction "1_1") (pintype "passive"))
      (node (ref "R8") (pin "2") (pinfunction "2_2") (pintype "passive"))
    )
    (net (code "65") (name "Net-(LED4-Pad1)") (class "Default")
      (node (ref "LED4") (pin "1") (pinfunction "1_1") (pintype "passive"))
      (node (ref "R9") (pin "2") (pinfunction "2_2") (pintype "passive"))
    )
    (net (code "66") (name "Net-(LED5-Pad1)") (class "Default")
      (node (ref "LED5") (pin "1") (pinfunction "1_1") (pintype "passive"))
      (node (ref "R10") (pin "2") (pinfunction "2_2") (pintype "passive"))
    )
    (net (code "67") (name "Net-(Q1-S)") (class "Default")
      (node (ref "F1") (pin "2") (pinfunction "2_2") (pintype "passive"))
      (node (ref "Q1") (pin "2") (pinfunction "S_2") (pintype "passive"))
    )
    (net (code "68") (name "Net-(SMPS-BOOT)") (class "Default")
      (node (ref "C2") (pin "1") (pinfunction "1_1") (pintype "passive"))
      (node (ref "SMPS") (pin "1") (pinfunction "BOOT_1") (pintype "passive"))
    )
    (net (code "69") (name "Net-(SMPS-ENA)") (class "Default")
      (node (ref "R3") (pin "2") (pinfunction "2_2") (pintype "passive"))
      (node (ref "R4") (pin "1") (pinfunction "1_1") (pintype "passive"))
      (node (ref "SMPS") (pin "5") (pinfunction "ENA_5") (pintype "passive"))
    )
    (net (code "70") (name "Net-(SMPS-VIN)") (class "Default")
      (node (ref "C1") (pin "1") (pinfunction "1_1") (pintype "passive"))
      (node (ref "FB1") (pin "2") (pinfunction "2_2") (pintype "passive"))
      (node (ref "SMPS") (pin "7") (pinfunction "VIN_7") (pintype "passive"))
    )
    (net (code "71") (name "Net-(SMPS-VSENSE)") (class "Default")
      (node (ref "R1") (pin "2") (pinfunction "2_2") (pintype "passive"))
      (node (ref "R2") (pin "2") (pinfunction "2_2") (pintype "passive"))
      (node (ref "SMPS") (pin "4") (pinfunction "VSENSE_4") (pintype "passive"))
    )
    (net (code "72") (name "unconnected-(CAN-VREF-Pad5)") (class "Default")
      (node (ref "CAN") (pin "5") (pinfunction "VREF_5") (pintype "passive"))
    )
    (net (code "73") (name "unconnected-(LCD-Pad12)") (class "Default")
      (node (ref "LCD") (pin "12") (pinfunction "12_12") (pintype "passive"))
    )
    (net (code "74") (name "unconnected-(LCD-Pad14)") (class "Default")
      (node (ref "LCD") (pin "14") (pinfunction "14_14") (pintype "passive"))
    )
    (net (code "75") (name "unconnected-(LCD-Pad18)") (class "Default")
      (node (ref "LCD") (pin "18") (pinfunction "18_18") (pintype "passive"))
    )
    (net (code "76") (name "unconnected-(LCD-Pad20)") (class "Default")
      (node (ref "LCD") (pin "20") (pinfunction "20_20") (pintype "passive"))
    )
    (net (code "77") (name "unconnected-(LCD-Pad23)") (class "Default")
      (node (ref "LCD") (pin "23") (pinfunction "23_23") (pintype "passive"))
    )
    (net (code "78") (name "unconnected-(LCD-Pad24)") (class "Default")
      (node (ref "LCD") (pin "24") (pinfunction "24_24") (pintype "passive"))
    )
    (net (code "79") (name "unconnected-(LCD-Pad25)") (class "Default")
      (node (ref "LCD") (pin "25") (pinfunction "25_25") (pintype "passive"))
    )
    (net (code "80") (name "unconnected-(LCD-Pad26)") (class "Default")
      (node (ref "LCD") (pin "26") (pinfunction "26_26") (pintype "passive"))
    )
    (net (code "81") (name "unconnected-(LCD-Pad27)") (class "Default")
      (node (ref "LCD") (pin "27") (pinfunction "27_27") (pintype "passive"))
    )
    (net (code "82") (name "unconnected-(LCD-Pad28)") (class "Default")
      (node (ref "LCD") (pin "28") (pinfunction "28_28") (pintype "passive"))
    )
    (net (code "83") (name "unconnected-(LCD-Pad30)") (class "Default")
      (node (ref "LCD") (pin "30") (pinfunction "30_30") (pintype "passive"))
    )
    (net (code "84") (name "unconnected-(MAIN-Pad5)") (class "Default")
      (node (ref "MAIN") (pin "5") (pinfunction "5_5") (pintype "passive"))
    )
    (net (code "85") (name "unconnected-(MAIN-Pad6)") (class "Default")
      (node (ref "MAIN") (pin "6") (pinfunction "6_6") (pintype "passive"))
    )
    (net (code "86") (name "unconnected-(SMPS-NC_1-Pad2)") (class "Default")
      (node (ref "SMPS") (pin "2") (pinfunction "NC_1_2") (pintype "passive"))
    )
    (net (code "87") (name "unconnected-(SMPS-NC_2-Pad3)") (class "Default")
      (node (ref "SMPS") (pin "3") (pinfunction "NC_2_3") (pintype "passive"))
    )
    (net (code "88") (name "unconnected-(STM32-BOOT0-Pad60)") (class "Default")
      (node (ref "STM32") (pin "60") (pinfunction "BOOT0_60") (pintype "passive"))
    )
    (net (code "89") (name "unconnected-(STM32-PA2-Pad16)") (class "Default")
      (node (ref "STM32") (pin "16") (pinfunction "PA2_16") (pintype "passive"))
    )
    (net (code "90") (name "unconnected-(STM32-PA3-Pad17)") (class "Default")
      (node (ref "STM32") (pin "17") (pinfunction "PA3_17") (pintype "passive"))
    )
    (net (code "91") (name "unconnected-(STM32-PA8-Pad41)") (class "Default")
      (node (ref "STM32") (pin "41") (pinfunction "PA8_41") (pintype "passive"))
    )
    (net (code "92") (name "unconnected-(STM32-PA15-Pad50)") (class "Default")
      (node (ref "STM32") (pin "50") (pinfunction "PA15_50") (pintype "passive"))
    )
    (net (code "93") (name "unconnected-(STM32-PB8-Pad61)") (class "Default")
      (node (ref "STM32") (pin "61") (pinfunction "PB8_61") (pintype "passive"))
    )
    (net (code "94") (name "unconnected-(STM32-PB9-Pad62)") (class "Default")
      (node (ref "STM32") (pin "62") (pinfunction "PB9_62") (pintype "passive"))
    )
    (net (code "95") (name "unconnected-(STM32-PB11-Pad30)") (class "Default")
      (node (ref "STM32") (pin "30") (pinfunction "PB11_30") (pintype "passive"))
    )
    (net (code "96") (name "unconnected-(STM32-PC10-Pad51)") (class "Default")
      (node (ref "STM32") (pin "51") (pinfunction "PC10_51") (pintype "passive"))
    )
    (net (code "97") (name "unconnected-(STM32-PC13-Pad2)") (class "Default")
      (node (ref "STM32") (pin "2") (pinfunction "PC13_2") (pintype "passive"))
    )
    (net (code "98") (name "unconnected-(STM32-PC14-OSC32_IN-Pad3)") (class "Default")
      (node (ref "STM32") (pin "3") (pinfunction "PC14-OSC32_IN_3") (pintype "passive"))
    )
    (net (code "99") (name "unconnected-(STM32-PC15-OSC32_OUT-Pad4)") (class "Default")
      (node (ref "STM32") (pin "4") (pinfunction "PC15-OSC32_OUT_4") (pintype "passive"))
    )
    (net (code "100") (name "unconnected-(STM32-PF0-OSC_IN-Pad5)") (class "Default")
      (node (ref "STM32") (pin "5") (pinfunction "PF0-OSC_IN_5") (pintype "passive"))
    )
    (net (code "101") (name "unconnected-(STM32-PF1-OSC_OUT-Pad6)") (class "Default")
      (node (ref "STM32") (pin "6") (pinfunction "PF1-OSC_OUT_6") (pintype "passive"))
    )
    (net (code "102") (name "unconnected-(STM32-VBAT-Pad1)") (class "Default")
      (node (ref "STM32") (pin "1") (pinfunction "VBAT_1") (pintype "passive"))
    )
    (net (code "103") (name "unconnected-(STM32-VDDA-Pad13)") (class "Default")
      (node (ref "STM32") (pin "13") (pinfunction "VDDA_13") (pintype "passive"))
    )
    (net (code "104") (name "unconnected-(STM32-VSSA-Pad12)") (class "Default")
      (node (ref "STM32") (pin "12") (pinfunction "VSSA_12") (pintype "passive"))
    )
    (net (code "105") (name "unconnected-(U2-EP-Pad25)") (class "Default")
      (node (ref "U2") (pin "25") (pinfunction "EP_25") (pintype "passive"))
    )
    (net (code "106") (name "unconnected-(U2-GPIO.0-Pad14)") (class "Default")
      (node (ref "U2") (pin "14") (pinfunction "GPIO.0_14") (pintype "passive"))
    )
    (net (code "107") (name "unconnected-(U2-GPIO.1-Pad13)") (class "Default")
      (node (ref "U2") (pin "13") (pinfunction "GPIO.1_13") (pintype "passive"))
    )
    (net (code "108") (name "unconnected-(U2-GPIO.2-Pad12)") (class "Default")
      (node (ref "U2") (pin "12") (pinfunction "GPIO.2_12") (pintype "passive"))
    )
    (net (code "109") (name "unconnected-(U2-GPIO.3-Pad11)") (class "Default")
      (node (ref "U2") (pin "11") (pinfunction "GPIO.3_11") (pintype "passive"))
    )
    (net (code "110") (name "unconnected-(U2-NC-Pad10)") (class "Default")
      (node (ref "U2") (pin "10") (pinfunction "NC_10") (pintype "passive"))
    )
    (net (code "111") (name "unconnected-(U2-RI-Pad1)") (class "Default")
      (node (ref "U2") (pin "1") (pinfunction "RI_1") (pintype "passive"))
    )
    (net (code "112") (name "unconnected-(U2-SUSPEND-Pad17)") (class "Default")
      (node (ref "U2") (pin "17") (pinfunction "SUSPEND_17") (pintype "passive"))
    )
    (net (code "113") (name "unconnected-(U2-VDD-Pad6)") (class "Default")
      (node (ref "U2") (pin "6") (pinfunction "VDD_6") (pintype "passive"))
    )
    (net (code "114") (name "unconnected-(U2-VIO-Pad5)") (class "Default")
      (node (ref "U2") (pin "5") (pinfunction "VIO_5") (pintype "passive"))
    )
    (net (code "115") (name "unconnected-(U2-VPP-Pad16)") (class "Default")
      (node (ref "U2") (pin "16") (pinfunction "VPP_16") (pintype "passive"))
    )
    (net (code "116") (name "unconnected-(U2-~{RST}-Pad9)") (class "Default")
      (node (ref "U2") (pin "9") (pinfunction "~{RST}_9") (pintype "passive"))
    )
    (net (code "117") (name "unconnected-(U2-~{SUSPEND}-Pad15)") (class "Default")
      (node (ref "U2") (pin "15") (pinfunction "~{SUSPEND}_15") (pintype "passive"))
    )
    (net (code "118") (name "unconnected-(U5-INT2-Pad11)") (class "Default")
      (node (ref "U5") (pin "11") (pinfunction "INT2_11") (pintype "passive"))
    )
    (net (code "119") (name "unconnected-(U5-NC-Pad5)") (class "Default")
      (node (ref "U5") (pin "5") (pinfunction "NC_5") (pintype "passive"))
    )
    (net (code "120") (name "unconnected-(USB-ID-Pad4)") (class "Default")
      (node (ref "USB") (pin "4") (pinfunction "ID_4") (pintype "passive"))
    )
  )
)
